# Sheet1.net
KiCad netlist of a schematic drawn in Altium Designer
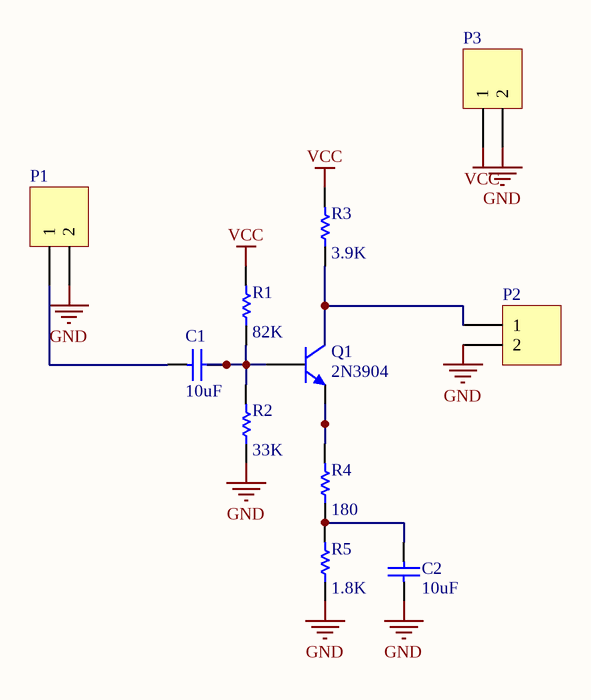
[diagram p0: Sheet1.SchDoc]

(export (version "E")
  (design (tool "Eeschema 10.0.6"))
  (components
    (comp (ref "C1")
      (value "10uF")
      (footprint "RAD-0.3")
      (description "Capacitor")
      (fields (field (name "Comment") "Cap") (field (name "PUBLISHER") "Altium Limited"))
      (libsource (lib "Miscellaneous Devices") (part "Cap"))
    )
    (comp (ref "C2")
      (value "10uF")
      (footprint "RAD-0.3")
      (description "Capacitor")
      (fields (field (name "Comment") "Cap") (field (name "PUBLISHER") "Altium Limited"))
      (libsource (lib "Miscellaneous Devices") (part "Cap"))
    )
    (comp (ref "P1")
      (value "Header 2H")
      (footprint "HDR1X2H")
      (description "Header, 2-Pin, Right Angle")
      (fields (field (name "PUBLISHER") "Altium Limited"))
      (libsource (lib "Miscellaneous Connectors") (part "Header 2H"))
    )
    (comp (ref "P2")
      (value "Header 2H")
      (footprint "HDR1X2H")
      (description "Header, 2-Pin, Right Angle")
      (fields (field (name "PUBLISHER") "Altium Limited"))
      (libsource (lib "") (part "Header 2H_1"))
    )
    (comp (ref "P3")
      (value "Header 2H")
      (footprint "HDR1X2H")
      (description "Header, 2-Pin, Right Angle")
      (fields (field (name "PUBLISHER") "Altium Limited"))
      (libsource (lib "Miscellaneous Connectors") (part "Header 2H"))
    )
    (comp (ref "Q1")
      (value "2N3904")
      (footprint "TO-92A")
      (description "NPN General Purpose Amplifier")
      (fields (field (name "PUBLISHER") "Altium Limited"))
      (libsource (lib "Miscellaneous Devices") (part "2N3904"))
    )
    (comp (ref "R1")
      (value "82K")
      (footprint "AXIAL-0.3")
      (description "Resistor")
      (fields (field (name "Comment") "Res1") (field (name "PUBLISHER") "Altium Limited"))
      (libsource (lib "Miscellaneous Devices") (part "Res1"))
    )
    (comp (ref "R2")
      (value "33K")
      (footprint "AXIAL-0.3")
      (description "Resistor")
      (fields (field (name "Comment") "Res1") (field (name "PUBLISHER") "Altium Limited"))
      (libsource (lib "Miscellaneous Devices") (part "Res1"))
    )
    (comp (ref "R3")
      (value "3.9K")
      (footprint "AXIAL-0.3")
      (description "Resistor")
      (fields (field (name "Comment") "Res1") (field (name "PUBLISHER") "Altium Limited"))
      (libsource (lib "Miscellaneous Devices") (part "Res1"))
    )
    (comp (ref "R4")
      (value "180")
      (footprint "AXIAL-0.3")
      (description "Resistor")
      (fields (field (name "Comment") "Res1") (field (name "PUBLISHER") "Altium Limited"))
      (libsource (lib "Miscellaneous Devices") (part "Res1"))
    )
    (comp (ref "R5")
      (value "1.8K")
      (footprint "AXIAL-0.3")
      (description "Resistor")
      (fields (field (name "Comment") "Res1") (field (name "PUBLISHER") "Altium Limited"))
      (libsource (lib "Miscellaneous Devices") (part "Res1"))
    )
  )
  (nets
    (net (code "1") (name "GND") (class "Default")
      (node (ref "C2") (pin "1") (pinfunction "1_1") (pintype "passive"))
      (node (ref "P1") (pin "2") (pinfunction "2_2") (pintype "passive"))
      (node (ref "P2") (pin "2") (pinfunction "2_2") (pintype "passive"))
      (node (ref "P3") (pin "2") (pinfunction "2_2") (pintype "passive"))
      (node (ref "R2") (pin "1") (pinfunction "1_1") (pintype "passive"))
      (node (ref "R5") (pin "1") (pinfunction "1_1") (pintype "passive"))
    )
    (net (code "2") (name "Net-(C1-Pad1)") (class "Default")
      (node (ref "C1") (pin "1") (pinfunction "1_1") (pintype "passive"))
      (node (ref "P1") (pin "1") (pinfunction "1_1") (pintype "passive"))
    )
    (net (code "3") (name "Net-(C2-Pad2)") (class "Default")
      (node (ref "C2") (pin "2") (pinfunction "2_2") (pintype "passive"))
      (node (ref "R4") (pin "1") (pinfunction "1_1") (pintype "passive"))
      (node (ref "R5") (pin "2") (pinfunction "2_2") (pintype "passive"))
    )
    (net (code "4") (name "Net-(Q1-B)") (class "Default")
      (node (ref "C1") (pin "2") (pinfunction "2_2") (pintype "passive"))
      (node (ref "Q1") (pin "2") (pinfunction "B_2") (pintype "passive"))
      (node (ref "R1") (pin "1") (pinfunction "1_1") (pintype "passive"))
      (node (ref "R2") (pin "2") (pinfunction "2_2") (pintype "passive"))
    )
    (net (code "5") (name "Net-(Q1-C)") (class "Default")
      (node (ref "P2") (pin "1") (pinfunction "1_1") (pintype "passive"))
      (node (ref "Q1") (pin "3") (pinfunction "C_3") (pintype "passive"))
      (node (ref "R3") (pin "1") (pinfunction "1_1") (pintype "passive"))
    )
    (net (code "6") (name "Net-(Q1-E)") (class "Default")
      (node (ref "Q1") (pin "1") (pinfunction "E_1") (pintype "passive"))
      (node (ref "R4") (pin "2") (pinfunction "2_2") (pintype "passive"))
    )
    (net (code "7") (name "VCC") (class "Default")
      (node (ref "P3") (pin "1") (pinfunction "1_1") (pintype "passive"))
      (node (ref "R1") (pin "2") (pinfunction "2_2") (pintype "passive"))
      (node (ref "R3") (pin "2") (pinfunction "2_2") (pintype "passive"))
    )
  )
)
